# EthernetMagJack.net
KiCad netlist of a schematic drawn in Altium Designer
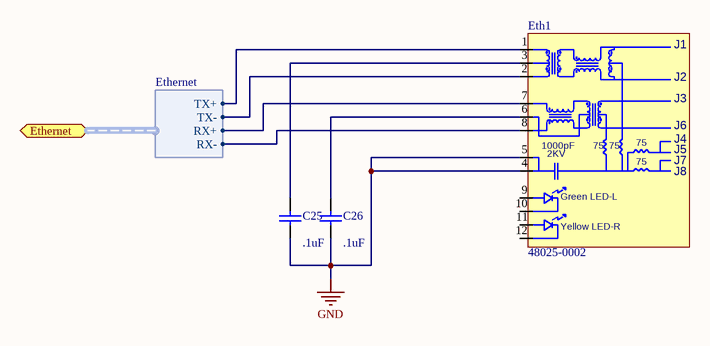
[diagram p0: EthernetMagJack.SchDoc]

(export (version "E")
  (design (tool "Eeschema 10.0.6"))
  (components
    (comp (ref "C25")
      (value ".1uF")
      (footprint "0402")
      (description "Capacitor (Semiconductor SIM Model)")
      (fields (field (name "Comment") "Cap Semi") (field (name "PUBLISHER") "Altium Limited"))
      (libsource (lib "Miscellaneous Devices") (part "Cap Semi"))
    )
    (comp (ref "C26")
      (value ".1uF")
      (footprint "0402")
      (description "Capacitor (Semiconductor SIM Model)")
      (fields (field (name "Comment") "Cap Semi") (field (name "PUBLISHER") "Altium Limited"))
      (libsource (lib "Miscellaneous Devices") (part "Cap Semi"))
    )
    (comp (ref "Eth1")
      (value "48025-0002")
      (footprint "MolexModularJacks:48025-0002")
      (description "Modular RJ45 Jack w/ Magnetics & LEDs")
      (fields (field (name "DIGIKEY PART NUMBER") "WM5449-ND"))
      (libsource (lib "MolexModularJacks") (part "48025-0002"))
    )
  )
  (nets
    (net (code "2") (name "/RX+") (class "Default")
      (node (ref "Eth1") (pin "7") (pinfunction "7_7") (pintype "passive"))
    )
    (net (code "3") (name "/RX-") (class "Default")
      (node (ref "Eth1") (pin "8") (pinfunction "8_8") (pintype "passive"))
    )
    (net (code "4") (name "/TX+") (class "Default")
      (node (ref "Eth1") (pin "1") (pinfunction "1_1") (pintype "passive"))
    )
    (net (code "5") (name "/TX-") (class "Default")
      (node (ref "Eth1") (pin "2") (pinfunction "2_2") (pintype "passive"))
    )
    (net (code "7") (name "GND") (class "Default")
      (node (ref "C25") (pin "1") (pinfunction "1_1") (pintype "passive"))
      (node (ref "C26") (pin "1") (pinfunction "1_1") (pintype "passive"))
      (node (ref "Eth1") (pin "4") (pinfunction "4_4") (pintype "passive"))
      (node (ref "Eth1") (pin "5") (pinfunction "5_5") (pintype "passive"))
    )
    (net (code "8") (name "Net-(C25-Pad2)") (class "Default")
      (node (ref "C25") (pin "2") (pinfunction "2_2") (pintype "passive"))
      (node (ref "Eth1") (pin "3") (pinfunction "3_3") (pintype "passive"))
    )
    (net (code "9") (name "Net-(C26-Pad2)") (class "Default")
      (node (ref "C26") (pin "2") (pinfunction "2_2") (pintype "passive"))
      (node (ref "Eth1") (pin "6") (pinfunction "6_6") (pintype "passive"))
    )
    (net (code "10") (name "unconnected-(Eth1-Pad9)") (class "Default")
      (node (ref "Eth1") (pin "9") (pinfunction "9_9") (pintype "passive"))
    )
    (net (code "11") (name "unconnected-(Eth1-Pad10)") (class "Default")
      (node (ref "Eth1") (pin "10") (pinfunction "10_10") (pintype "passive"))
    )
    (net (code "12") (name "unconnected-(Eth1-Pad11)") (class "Default")
      (node (ref "Eth1") (pin "11") (pinfunction "11_11") (pintype "passive"))
    )
    (net (code "13") (name "unconnected-(Eth1-Pad12)") (class "Default")
      (node (ref "Eth1") (pin "12") (pinfunction "12_12") (pintype "passive"))
    )
  )
)
